# PC.net
KiCad netlist of a schematic drawn in EAGLE
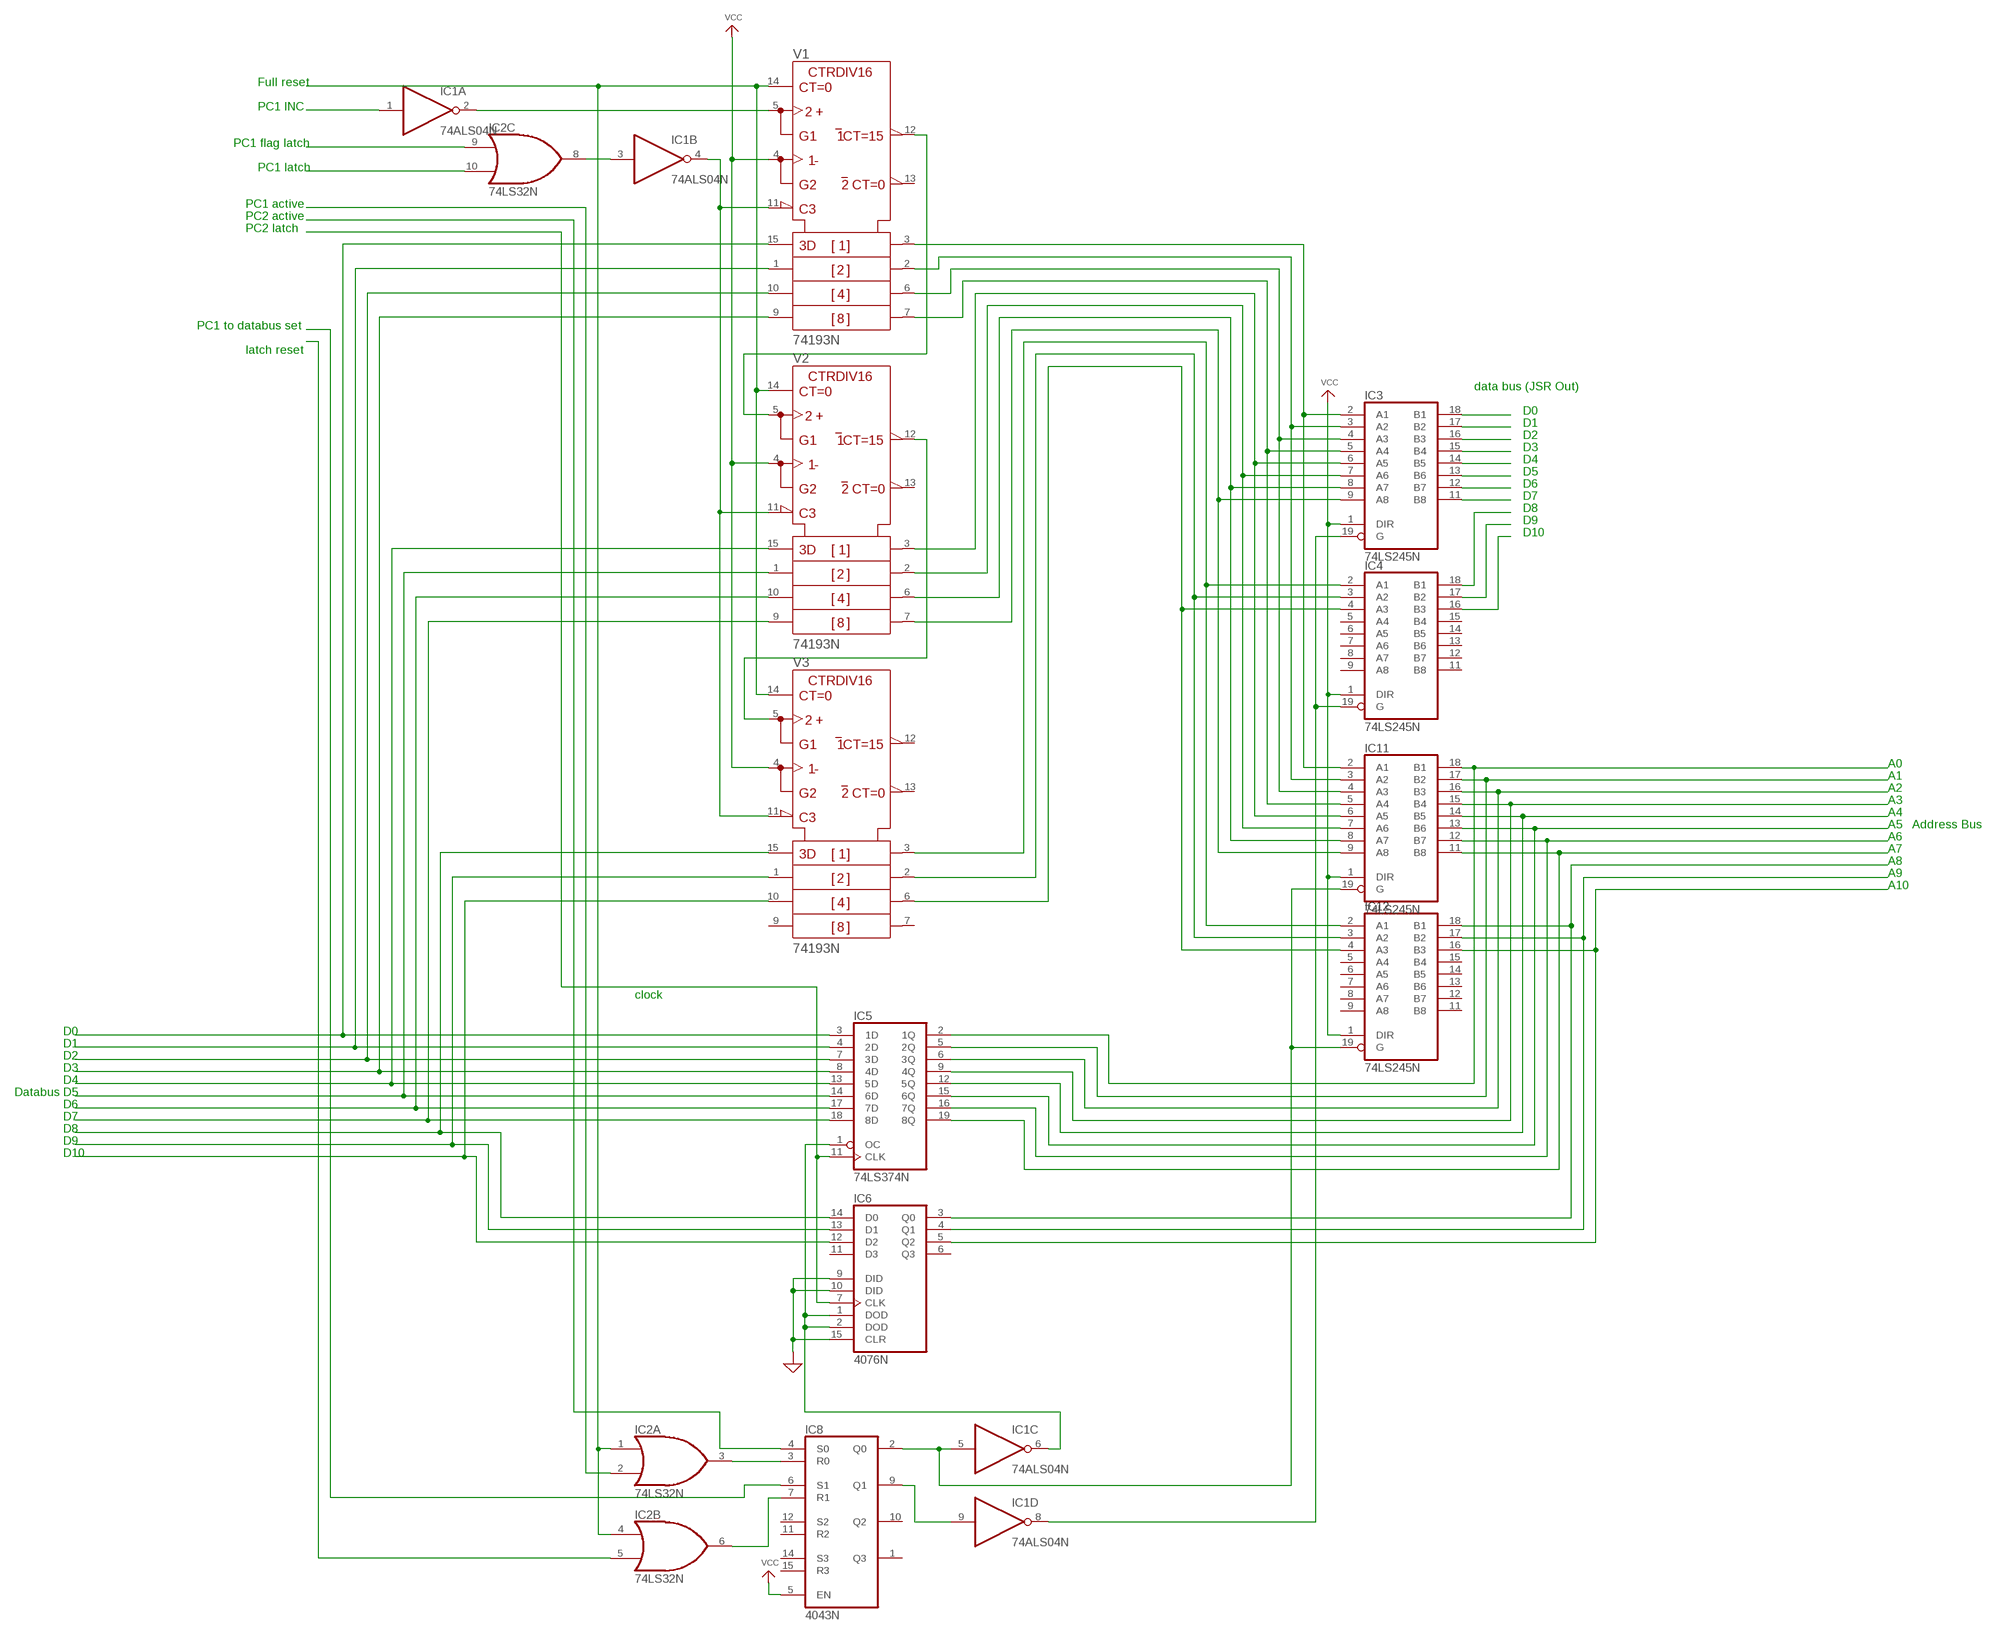
[diagram p0: schematic, sheet 1]

(export (version "E")
  (design (tool "Eeschema 10.0.6"))
  (components
    (comp (ref "IC1")
      (value "74ALS04N")
      (footprint "eagle-import:DIL14")
      (libsource (lib "eagle-import") (part "7404NALS"))
    )
    (comp (ref "IC2")
      (value "74LS32N")
      (footprint "eagle-import:DIL14")
      (libsource (lib "eagle-import") (part "7432NLS"))
    )
    (comp (ref "IC3")
      (value "74LS245N")
      (footprint "eagle-import:DIL20")
      (libsource (lib "eagle-import") (part "74245NLS"))
    )
    (comp (ref "IC4")
      (value "74LS245N")
      (footprint "eagle-import:DIL20")
      (libsource (lib "eagle-import") (part "74245NLS"))
    )
    (comp (ref "IC5")
      (value "74LS374N")
      (footprint "eagle-import:DIL20")
      (libsource (lib "eagle-import") (part "74374NLS"))
    )
    (comp (ref "IC6")
      (value "4076N")
      (footprint "eagle-import:DIL16")
      (libsource (lib "eagle-import") (part "4076N"))
    )
    (comp (ref "IC8")
      (value "4043N")
      (footprint "eagle-import:DIL16")
      (libsource (lib "eagle-import") (part "4043N"))
    )
    (comp (ref "IC11")
      (value "74LS245N")
      (footprint "eagle-import:DIL20")
      (libsource (lib "eagle-import") (part "74245NLS"))
    )
    (comp (ref "IC12")
      (value "74LS245N")
      (footprint "eagle-import:DIL20")
      (libsource (lib "eagle-import") (part "74245NLS"))
    )
    (comp (ref "V1")
      (value "74193N")
      (footprint "eagle-import:DIL16")
      (libsource (lib "eagle-import") (part "74193N"))
    )
    (comp (ref "V2")
      (value "74193N")
      (footprint "eagle-import:DIL16")
      (libsource (lib "eagle-import") (part "74193N"))
    )
    (comp (ref "V3")
      (value "74193N")
      (footprint "eagle-import:DIL16")
      (libsource (lib "eagle-import") (part "74193N"))
    )
  )
  (nets
    (net (code "1") (name "Net-(IC1A-O)") (class "Default")
      (node (ref "IC1") (pin "2") (pinfunction "O_2") (pintype "output"))
      (node (ref "V1") (pin "5") (pinfunction "UP_5") (pintype "input"))
    )
    (net (code "2") (name "Net-(IC1B-I)") (class "Default")
      (node (ref "IC1") (pin "3") (pinfunction "I_3") (pintype "input"))
      (node (ref "IC2") (pin "8") (pinfunction "O_8") (pintype "output"))
    )
    (net (code "3") (name "Net-(IC1B-O)") (class "Default")
      (node (ref "IC1") (pin "4") (pinfunction "O_4") (pintype "output"))
      (node (ref "V1") (pin "11") (pinfunction "~{LOAD}_11") (pintype "input"))
      (node (ref "V2") (pin "11") (pinfunction "~{LOAD}_11") (pintype "input"))
      (node (ref "V3") (pin "11") (pinfunction "~{LOAD}_11") (pintype "input"))
    )
    (net (code "4") (name "Net-(IC1C-O)") (class "Default")
      (node (ref "IC1") (pin "6") (pinfunction "O_6") (pintype "output"))
      (node (ref "IC5") (pin "1") (pinfunction "OC_1") (pintype "input"))
      (node (ref "IC6") (pin "1") (pinfunction "DOD_1") (pintype "input"))
      (node (ref "IC6") (pin "2") (pinfunction "DOD_2") (pintype "input"))
    )
    (net (code "5") (name "Net-(IC1D-I)") (class "Default")
      (node (ref "IC1") (pin "9") (pinfunction "I_9") (pintype "input"))
      (node (ref "IC8") (pin "9") (pinfunction "Q1_9") (pintype "output"))
    )
    (net (code "6") (name "Net-(IC1D-O)") (class "Default")
      (node (ref "IC1") (pin "8") (pinfunction "O_8") (pintype "output"))
      (node (ref "IC3") (pin "19") (pinfunction "G_19") (pintype "input"))
      (node (ref "IC4") (pin "19") (pinfunction "G_19") (pintype "input"))
    )
    (net (code "7") (name "Net-(IC2A-I0)") (class "Default")
      (node (ref "IC2") (pin "1") (pinfunction "I0_1") (pintype "input"))
      (node (ref "IC2") (pin "4") (pinfunction "I0_4") (pintype "input"))
      (node (ref "V1") (pin "14") (pinfunction "CLR_14") (pintype "input"))
      (node (ref "V2") (pin "14") (pinfunction "CLR_14") (pintype "input"))
      (node (ref "V3") (pin "14") (pinfunction "CLR_14") (pintype "input"))
    )
    (net (code "8") (name "Net-(IC2A-O)") (class "Default")
      (node (ref "IC2") (pin "3") (pinfunction "O_3") (pintype "output"))
      (node (ref "IC8") (pin "3") (pinfunction "R0_3") (pintype "input"))
    )
    (net (code "9") (name "Net-(IC2B-O)") (class "Default")
      (node (ref "IC2") (pin "6") (pinfunction "O_6") (pintype "output"))
      (node (ref "IC8") (pin "7") (pinfunction "R1_7") (pintype "input"))
    )
    (net (code "10") (name "Net-(IC5A-1D)") (class "Default")
      (node (ref "IC5") (pin "3") (pinfunction "1D_3") (pintype "input"))
      (node (ref "V1") (pin "15") (pinfunction "A_15") (pintype "input"))
    )
    (net (code "11") (name "Net-(IC5A-2D)") (class "Default")
      (node (ref "IC5") (pin "4") (pinfunction "2D_4") (pintype "input"))
      (node (ref "V1") (pin "1") (pinfunction "B_1") (pintype "input"))
    )
    (net (code "12") (name "Net-(IC5A-3D)") (class "Default")
      (node (ref "IC5") (pin "7") (pinfunction "3D_7") (pintype "input"))
      (node (ref "V1") (pin "10") (pinfunction "C_10") (pintype "input"))
    )
    (net (code "13") (name "Net-(IC5A-4D)") (class "Default")
      (node (ref "IC5") (pin "8") (pinfunction "4D_8") (pintype "input"))
      (node (ref "V1") (pin "9") (pinfunction "D_9") (pintype "input"))
    )
    (net (code "14") (name "Net-(IC5A-5D)") (class "Default")
      (node (ref "IC5") (pin "13") (pinfunction "5D_13") (pintype "input"))
      (node (ref "V2") (pin "15") (pinfunction "A_15") (pintype "input"))
    )
    (net (code "15") (name "Net-(IC5A-6D)") (class "Default")
      (node (ref "IC5") (pin "14") (pinfunction "6D_14") (pintype "input"))
      (node (ref "V2") (pin "1") (pinfunction "B_1") (pintype "input"))
    )
    (net (code "16") (name "Net-(IC5A-7D)") (class "Default")
      (node (ref "IC5") (pin "17") (pinfunction "7D_17") (pintype "input"))
      (node (ref "V2") (pin "10") (pinfunction "C_10") (pintype "input"))
    )
    (net (code "17") (name "Net-(IC5A-8D)") (class "Default")
      (node (ref "IC5") (pin "18") (pinfunction "8D_18") (pintype "input"))
      (node (ref "V2") (pin "9") (pinfunction "D_9") (pintype "input"))
    )
    (net (code "18") (name "Net-(IC5A-CLK)") (class "Default")
      (node (ref "IC5") (pin "11") (pinfunction "CLK_11") (pintype "input"))
      (node (ref "IC6") (pin "7") (pinfunction "CLK_7") (pintype "input"))
    )
    (net (code "19") (name "Net-(IC6A-D0)") (class "Default")
      (node (ref "IC6") (pin "14") (pinfunction "D0_14") (pintype "input"))
      (node (ref "V3") (pin "15") (pinfunction "A_15") (pintype "input"))
    )
    (net (code "20") (name "Net-(IC6A-D1)") (class "Default")
      (node (ref "IC6") (pin "13") (pinfunction "D1_13") (pintype "input"))
      (node (ref "V3") (pin "1") (pinfunction "B_1") (pintype "input"))
    )
    (net (code "21") (name "Net-(IC6A-D2)") (class "Default")
      (node (ref "IC6") (pin "12") (pinfunction "D2_12") (pintype "input"))
      (node (ref "V3") (pin "10") (pinfunction "C_10") (pintype "input"))
    )
    (net (code "22") (name "Net-(IC11A-A1)") (class "Default")
      (node (ref "IC11") (pin "2") (pinfunction "A1_2") (pintype "bidirectional"))
      (node (ref "IC3") (pin "2") (pinfunction "A1_2") (pintype "bidirectional"))
      (node (ref "V1") (pin "3") (pinfunction "QA_3") (pintype "output"))
    )
    (net (code "23") (name "Net-(IC11A-A2)") (class "Default")
      (node (ref "IC11") (pin "3") (pinfunction "A2_3") (pintype "bidirectional"))
      (node (ref "IC3") (pin "3") (pinfunction "A2_3") (pintype "bidirectional"))
      (node (ref "V1") (pin "2") (pinfunction "QB_2") (pintype "output"))
    )
    (net (code "24") (name "Net-(IC11A-A3)") (class "Default")
      (node (ref "IC11") (pin "4") (pinfunction "A3_4") (pintype "bidirectional"))
      (node (ref "IC3") (pin "4") (pinfunction "A3_4") (pintype "bidirectional"))
      (node (ref "V1") (pin "6") (pinfunction "QC_6") (pintype "output"))
    )
    (net (code "25") (name "Net-(IC11A-A4)") (class "Default")
      (node (ref "IC11") (pin "5") (pinfunction "A4_5") (pintype "bidirectional"))
      (node (ref "IC3") (pin "5") (pinfunction "A4_5") (pintype "bidirectional"))
      (node (ref "V1") (pin "7") (pinfunction "QD_7") (pintype "output"))
    )
    (net (code "26") (name "Net-(IC11A-A5)") (class "Default")
      (node (ref "IC11") (pin "6") (pinfunction "A5_6") (pintype "bidirectional"))
      (node (ref "IC3") (pin "6") (pinfunction "A5_6") (pintype "bidirectional"))
      (node (ref "V2") (pin "3") (pinfunction "QA_3") (pintype "output"))
    )
    (net (code "27") (name "Net-(IC11A-A6)") (class "Default")
      (node (ref "IC11") (pin "7") (pinfunction "A6_7") (pintype "bidirectional"))
      (node (ref "IC3") (pin "7") (pinfunction "A6_7") (pintype "bidirectional"))
      (node (ref "V2") (pin "2") (pinfunction "QB_2") (pintype "output"))
    )
    (net (code "28") (name "Net-(IC11A-A7)") (class "Default")
      (node (ref "IC11") (pin "8") (pinfunction "A7_8") (pintype "bidirectional"))
      (node (ref "IC3") (pin "8") (pinfunction "A7_8") (pintype "bidirectional"))
      (node (ref "V2") (pin "6") (pinfunction "QC_6") (pintype "output"))
    )
    (net (code "29") (name "Net-(IC11A-A8)") (class "Default")
      (node (ref "IC11") (pin "9") (pinfunction "A8_9") (pintype "bidirectional"))
      (node (ref "IC3") (pin "9") (pinfunction "A8_9") (pintype "bidirectional"))
      (node (ref "V2") (pin "7") (pinfunction "QD_7") (pintype "output"))
    )
    (net (code "30") (name "Net-(IC11A-B1)") (class "Default")
      (node (ref "IC11") (pin "18") (pinfunction "B1_18") (pintype "bidirectional"))
      (node (ref "IC5") (pin "2") (pinfunction "1Q_2") (pintype "tri_state"))
    )
    (net (code "31") (name "Net-(IC11A-B2)") (class "Default")
      (node (ref "IC11") (pin "17") (pinfunction "B2_17") (pintype "bidirectional"))
      (node (ref "IC5") (pin "5") (pinfunction "2Q_5") (pintype "tri_state"))
    )
    (net (code "32") (name "Net-(IC11A-B3)") (class "Default")
      (node (ref "IC11") (pin "16") (pinfunction "B3_16") (pintype "bidirectional"))
      (node (ref "IC5") (pin "6") (pinfunction "3Q_6") (pintype "tri_state"))
    )
    (net (code "33") (name "Net-(IC11A-B4)") (class "Default")
      (node (ref "IC11") (pin "15") (pinfunction "B4_15") (pintype "bidirectional"))
      (node (ref "IC5") (pin "9") (pinfunction "4Q_9") (pintype "tri_state"))
    )
    (net (code "34") (name "Net-(IC11A-B5)") (class "Default")
      (node (ref "IC11") (pin "14") (pinfunction "B5_14") (pintype "bidirectional"))
      (node (ref "IC5") (pin "12") (pinfunction "5Q_12") (pintype "tri_state"))
    )
    (net (code "35") (name "Net-(IC11A-B6)") (class "Default")
      (node (ref "IC11") (pin "13") (pinfunction "B6_13") (pintype "bidirectional"))
      (node (ref "IC5") (pin "15") (pinfunction "6Q_15") (pintype "tri_state"))
    )
    (net (code "36") (name "Net-(IC11A-B7)") (class "Default")
      (node (ref "IC11") (pin "12") (pinfunction "B7_12") (pintype "bidirectional"))
      (node (ref "IC5") (pin "16") (pinfunction "7Q_16") (pintype "tri_state"))
    )
    (net (code "37") (name "Net-(IC11A-B8)") (class "Default")
      (node (ref "IC11") (pin "11") (pinfunction "B8_11") (pintype "bidirectional"))
      (node (ref "IC5") (pin "19") (pinfunction "8Q_19") (pintype "tri_state"))
    )
    (net (code "38") (name "Net-(IC11A-G)") (class "Default")
      (node (ref "IC1") (pin "5") (pinfunction "I_5") (pintype "input"))
      (node (ref "IC11") (pin "19") (pinfunction "G_19") (pintype "input"))
      (node (ref "IC12") (pin "19") (pinfunction "G_19") (pintype "input"))
      (node (ref "IC8") (pin "2") (pinfunction "Q0_2") (pintype "output"))
    )
    (net (code "39") (name "Net-(IC12A-A1)") (class "Default")
      (node (ref "IC12") (pin "2") (pinfunction "A1_2") (pintype "bidirectional"))
      (node (ref "IC4") (pin "2") (pinfunction "A1_2") (pintype "bidirectional"))
      (node (ref "V3") (pin "3") (pinfunction "QA_3") (pintype "output"))
    )
    (net (code "40") (name "Net-(IC12A-A2)") (class "Default")
      (node (ref "IC12") (pin "3") (pinfunction "A2_3") (pintype "bidirectional"))
      (node (ref "IC4") (pin "3") (pinfunction "A2_3") (pintype "bidirectional"))
      (node (ref "V3") (pin "2") (pinfunction "QB_2") (pintype "output"))
    )
    (net (code "41") (name "Net-(IC12A-A3)") (class "Default")
      (node (ref "IC12") (pin "4") (pinfunction "A3_4") (pintype "bidirectional"))
      (node (ref "IC4") (pin "4") (pinfunction "A3_4") (pintype "bidirectional"))
      (node (ref "V3") (pin "6") (pinfunction "QC_6") (pintype "output"))
    )
    (net (code "42") (name "Net-(IC12A-B1)") (class "Default")
      (node (ref "IC12") (pin "18") (pinfunction "B1_18") (pintype "bidirectional"))
      (node (ref "IC6") (pin "3") (pinfunction "Q0_3") (pintype "output"))
    )
    (net (code "43") (name "Net-(IC12A-B2)") (class "Default")
      (node (ref "IC12") (pin "17") (pinfunction "B2_17") (pintype "bidirectional"))
      (node (ref "IC6") (pin "4") (pinfunction "Q1_4") (pintype "output"))
    )
    (net (code "44") (name "Net-(IC12A-B3)") (class "Default")
      (node (ref "IC12") (pin "16") (pinfunction "B3_16") (pintype "bidirectional"))
      (node (ref "IC6") (pin "5") (pinfunction "Q2_5") (pintype "output"))
    )
    (net (code "45") (name "Net-(V1C-~{CO})") (class "Default")
      (node (ref "V1") (pin "12") (pinfunction "~{CO}_12") (pintype "output"))
      (node (ref "V2") (pin "5") (pinfunction "UP_5") (pintype "input"))
    )
    (net (code "46") (name "Net-(V2C-~{CO})") (class "Default")
      (node (ref "V2") (pin "12") (pinfunction "~{CO}_12") (pintype "output"))
      (node (ref "V3") (pin "5") (pinfunction "UP_5") (pintype "input"))
    )
    (net (code "47") (name "SUP") (class "Default")
      (node (ref "IC6") (pin "10") (pinfunction "DID_10") (pintype "input"))
      (node (ref "IC6") (pin "15") (pinfunction "CLR_15") (pintype "input"))
      (node (ref "IC6") (pin "9") (pinfunction "DID_9") (pintype "input"))
    )
    (net (code "48") (name "VCC") (class "Default")
      (node (ref "IC11") (pin "1") (pinfunction "DIR_1") (pintype "input"))
      (node (ref "IC12") (pin "1") (pinfunction "DIR_1") (pintype "input"))
      (node (ref "IC3") (pin "1") (pinfunction "DIR_1") (pintype "input"))
      (node (ref "IC4") (pin "1") (pinfunction "DIR_1") (pintype "input"))
      (node (ref "IC8") (pin "5") (pinfunction "EN_5") (pintype "input"))
      (node (ref "V1") (pin "4") (pinfunction "DOWN_4") (pintype "input"))
      (node (ref "V2") (pin "4") (pinfunction "DOWN_4") (pintype "input"))
      (node (ref "V3") (pin "4") (pinfunction "DOWN_4") (pintype "input"))
    )
    (net (code "49") (name "unconnected-(IC1A-I-Pad1)") (class "Default")
      (node (ref "IC1") (pin "1") (pinfunction "I_1") (pintype "input"))
    )
    (net (code "50") (name "unconnected-(IC2A-I1-Pad2)") (class "Default")
      (node (ref "IC2") (pin "2") (pinfunction "I1_2") (pintype "input"))
    )
    (net (code "51") (name "unconnected-(IC2B-I1-Pad5)") (class "Default")
      (node (ref "IC2") (pin "5") (pinfunction "I1_5") (pintype "input"))
    )
    (net (code "52") (name "unconnected-(IC2C-I0-Pad9)") (class "Default")
      (node (ref "IC2") (pin "9") (pinfunction "I0_9") (pintype "input"))
    )
    (net (code "53") (name "unconnected-(IC2C-I1-Pad10)") (class "Default")
      (node (ref "IC2") (pin "10") (pinfunction "I1_10") (pintype "input"))
    )
    (net (code "54") (name "unconnected-(IC3A-B1-Pad18)") (class "Default")
      (node (ref "IC3") (pin "18") (pinfunction "B1_18") (pintype "bidirectional"))
    )
    (net (code "55") (name "unconnected-(IC3A-B2-Pad17)") (class "Default")
      (node (ref "IC3") (pin "17") (pinfunction "B2_17") (pintype "bidirectional"))
    )
    (net (code "56") (name "unconnected-(IC3A-B3-Pad16)") (class "Default")
      (node (ref "IC3") (pin "16") (pinfunction "B3_16") (pintype "bidirectional"))
    )
    (net (code "57") (name "unconnected-(IC3A-B4-Pad15)") (class "Default")
      (node (ref "IC3") (pin "15") (pinfunction "B4_15") (pintype "bidirectional"))
    )
    (net (code "58") (name "unconnected-(IC3A-B5-Pad14)") (class "Default")
      (node (ref "IC3") (pin "14") (pinfunction "B5_14") (pintype "bidirectional"))
    )
    (net (code "59") (name "unconnected-(IC3A-B6-Pad13)") (class "Default")
      (node (ref "IC3") (pin "13") (pinfunction "B6_13") (pintype "bidirectional"))
    )
    (net (code "60") (name "unconnected-(IC3A-B7-Pad12)") (class "Default")
      (node (ref "IC3") (pin "12") (pinfunction "B7_12") (pintype "bidirectional"))
    )
    (net (code "61") (name "unconnected-(IC3A-B8-Pad11)") (class "Default")
      (node (ref "IC3") (pin "11") (pinfunction "B8_11") (pintype "bidirectional"))
    )
    (net (code "62") (name "unconnected-(IC4A-A4-Pad5)") (class "Default")
      (node (ref "IC4") (pin "5") (pinfunction "A4_5") (pintype "bidirectional"))
    )
    (net (code "63") (name "unconnected-(IC4A-A5-Pad6)") (class "Default")
      (node (ref "IC4") (pin "6") (pinfunction "A5_6") (pintype "bidirectional"))
    )
    (net (code "64") (name "unconnected-(IC4A-A6-Pad7)") (class "Default")
      (node (ref "IC4") (pin "7") (pinfunction "A6_7") (pintype "bidirectional"))
    )
    (net (code "65") (name "unconnected-(IC4A-A7-Pad8)") (class "Default")
      (node (ref "IC4") (pin "8") (pinfunction "A7_8") (pintype "bidirectional"))
    )
    (net (code "66") (name "unconnected-(IC4A-A8-Pad9)") (class "Default")
      (node (ref "IC4") (pin "9") (pinfunction "A8_9") (pintype "bidirectional"))
    )
    (net (code "67") (name "unconnected-(IC4A-B1-Pad18)") (class "Default")
      (node (ref "IC4") (pin "18") (pinfunction "B1_18") (pintype "bidirectional"))
    )
    (net (code "68") (name "unconnected-(IC4A-B2-Pad17)") (class "Default")
      (node (ref "IC4") (pin "17") (pinfunction "B2_17") (pintype "bidirectional"))
    )
    (net (code "69") (name "unconnected-(IC4A-B3-Pad16)") (class "Default")
      (node (ref "IC4") (pin "16") (pinfunction "B3_16") (pintype "bidirectional"))
    )
    (net (code "70") (name "unconnected-(IC4A-B4-Pad15)") (class "Default")
      (node (ref "IC4") (pin "15") (pinfunction "B4_15") (pintype "bidirectional"))
    )
    (net (code "71") (name "unconnected-(IC4A-B5-Pad14)") (class "Default")
      (node (ref "IC4") (pin "14") (pinfunction "B5_14") (pintype "bidirectional"))
    )
    (net (code "72") (name "unconnected-(IC4A-B6-Pad13)") (class "Default")
      (node (ref "IC4") (pin "13") (pinfunction "B6_13") (pintype "bidirectional"))
    )
    (net (code "73") (name "unconnected-(IC4A-B7-Pad12)") (class "Default")
      (node (ref "IC4") (pin "12") (pinfunction "B7_12") (pintype "bidirectional"))
    )
    (net (code "74") (name "unconnected-(IC4A-B8-Pad11)") (class "Default")
      (node (ref "IC4") (pin "11") (pinfunction "B8_11") (pintype "bidirectional"))
    )
    (net (code "75") (name "unconnected-(IC6A-D3-Pad11)") (class "Default")
      (node (ref "IC6") (pin "11") (pinfunction "D3_11") (pintype "input"))
    )
    (net (code "76") (name "unconnected-(IC6A-Q3-Pad6)") (class "Default")
      (node (ref "IC6") (pin "6") (pinfunction "Q3_6") (pintype "output"))
    )
    (net (code "77") (name "unconnected-(IC8A-Q2-Pad10)") (class "Default")
      (node (ref "IC8") (pin "10") (pinfunction "Q2_10") (pintype "output"))
    )
    (net (code "78") (name "unconnected-(IC8A-Q3-Pad1)") (class "Default")
      (node (ref "IC8") (pin "1") (pinfunction "Q3_1") (pintype "output"))
    )
    (net (code "79") (name "unconnected-(IC8A-R2-Pad11)") (class "Default")
      (node (ref "IC8") (pin "11") (pinfunction "R2_11") (pintype "input"))
    )
    (net (code "80") (name "unconnected-(IC8A-R3-Pad15)") (class "Default")
      (node (ref "IC8") (pin "15") (pinfunction "R3_15") (pintype "input"))
    )
    (net (code "81") (name "unconnected-(IC8A-S0-Pad4)") (class "Default")
      (node (ref "IC8") (pin "4") (pinfunction "S0_4") (pintype "input"))
    )
    (net (code "82") (name "unconnected-(IC8A-S1-Pad6)") (class "Default")
      (node (ref "IC8") (pin "6") (pinfunction "S1_6") (pintype "input"))
    )
    (net (code "83") (name "unconnected-(IC8A-S2-Pad12)") (class "Default")
      (node (ref "IC8") (pin "12") (pinfunction "S2_12") (pintype "input"))
    )
    (net (code "84") (name "unconnected-(IC8A-S3-Pad14)") (class "Default")
      (node (ref "IC8") (pin "14") (pinfunction "S3_14") (pintype "input"))
    )
    (net (code "85") (name "unconnected-(IC12A-A4-Pad5)") (class "Default")
      (node (ref "IC12") (pin "5") (pinfunction "A4_5") (pintype "bidirectional"))
    )
    (net (code "86") (name "unconnected-(IC12A-A5-Pad6)") (class "Default")
      (node (ref "IC12") (pin "6") (pinfunction "A5_6") (pintype "bidirectional"))
    )
    (net (code "87") (name "unconnected-(IC12A-A6-Pad7)") (class "Default")
      (node (ref "IC12") (pin "7") (pinfunction "A6_7") (pintype "bidirectional"))
    )
    (net (code "88") (name "unconnected-(IC12A-A7-Pad8)") (class "Default")
      (node (ref "IC12") (pin "8") (pinfunction "A7_8") (pintype "bidirectional"))
    )
    (net (code "89") (name "unconnected-(IC12A-A8-Pad9)") (class "Default")
      (node (ref "IC12") (pin "9") (pinfunction "A8_9") (pintype "bidirectional"))
    )
    (net (code "90") (name "unconnected-(IC12A-B4-Pad15)") (class "Default")
      (node (ref "IC12") (pin "15") (pinfunction "B4_15") (pintype "bidirectional"))
    )
    (net (code "91") (name "unconnected-(IC12A-B5-Pad14)") (class "Default")
      (node (ref "IC12") (pin "14") (pinfunction "B5_14") (pintype "bidirectional"))
    )
    (net (code "92") (name "unconnected-(IC12A-B6-Pad13)") (class "Default")
      (node (ref "IC12") (pin "13") (pinfunction "B6_13") (pintype "bidirectional"))
    )
    (net (code "93") (name "unconnected-(IC12A-B7-Pad12)") (class "Default")
      (node (ref "IC12") (pin "12") (pinfunction "B7_12") (pintype "bidirectional"))
    )
    (net (code "94") (name "unconnected-(IC12A-B8-Pad11)") (class "Default")
      (node (ref "IC12") (pin "11") (pinfunction "B8_11") (pintype "bidirectional"))
    )
    (net (code "95") (name "unconnected-(V1C-~{BO}-Pad13)") (class "Default")
      (node (ref "V1") (pin "13") (pinfunction "~{BO}_13") (pintype "output"))
    )
    (net (code "96") (name "unconnected-(V2C-~{BO}-Pad13)") (class "Default")
      (node (ref "V2") (pin "13") (pinfunction "~{BO}_13") (pintype "output"))
    )
    (net (code "97") (name "unconnected-(V3C-D-Pad9)") (class "Default")
      (node (ref "V3") (pin "9") (pinfunction "D_9") (pintype "input"))
    )
    (net (code "98") (name "unconnected-(V3C-QD-Pad7)") (class "Default")
      (node (ref "V3") (pin "7") (pinfunction "QD_7") (pintype "output"))
    )
    (net (code "99") (name "unconnected-(V3C-~{BO}-Pad13)") (class "Default")
      (node (ref "V3") (pin "13") (pinfunction "~{BO}_13") (pintype "output"))
    )
    (net (code "100") (name "unconnected-(V3C-~{CO}-Pad12)") (class "Default")
      (node (ref "V3") (pin "12") (pinfunction "~{CO}_12") (pintype "output"))
    )
  )
)
